# GPS_radiologger_v24_L70_CMWX_MAX.net
KiCad netlist of a schematic drawn in EAGLE
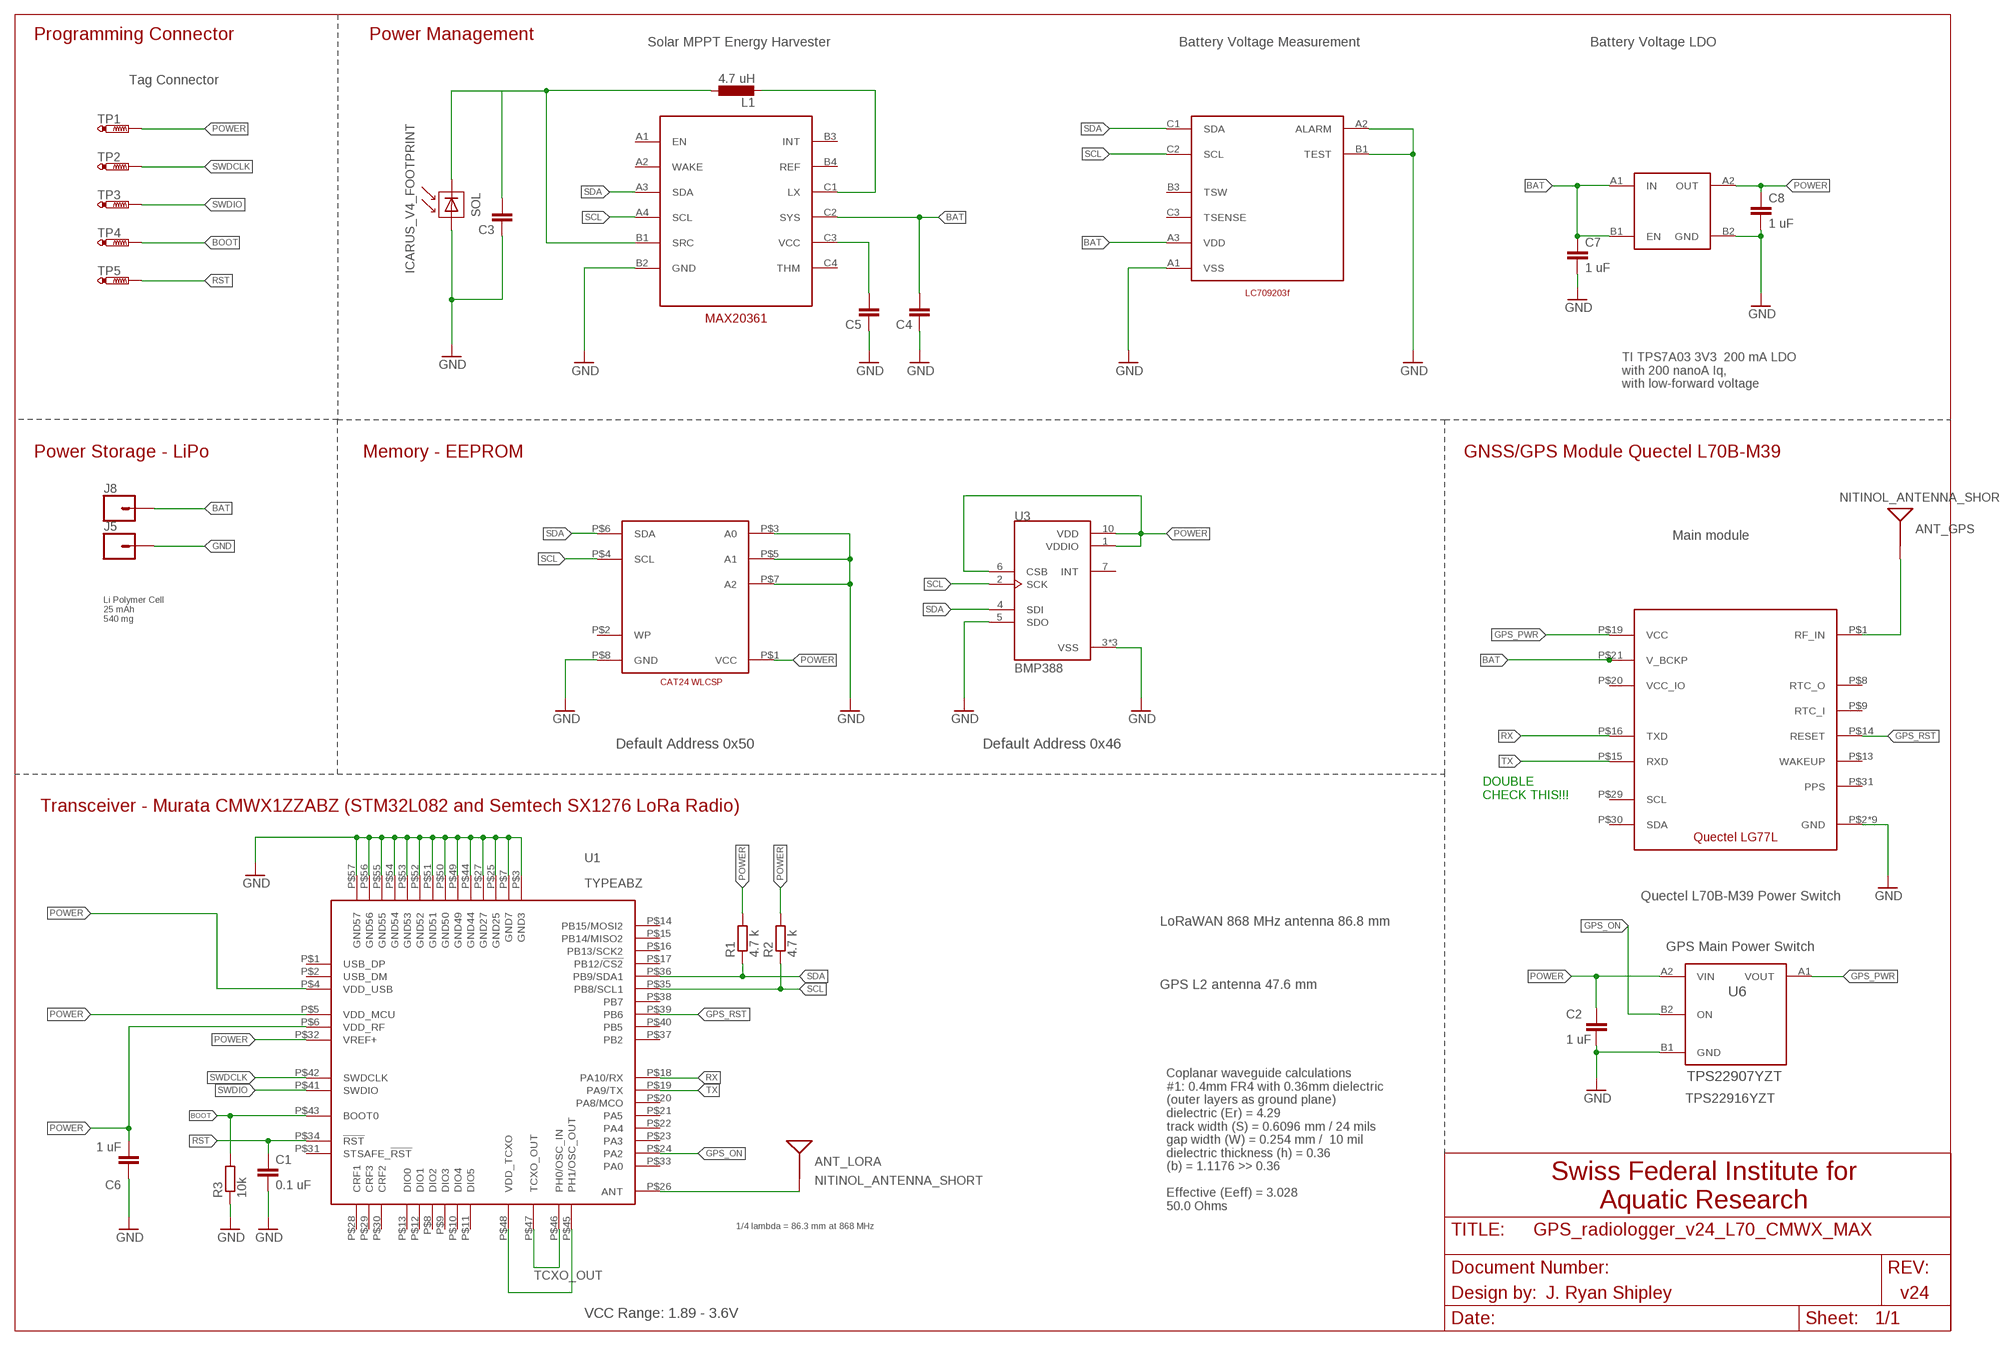
[diagram p0: schematic, sheet 1]

(export (version "E")
  (design (tool "Eeschema 10.0.6"))
  (components
    (comp (ref "ANT_GPS")
      (value "NITINOL_ANTENNA_SHORT")
      (footprint "eagle-import:ICARUS_NITINOL_ANTENNA_SHORT")
      (libsource (lib "eagle-import") (part "NITINOL_ANTENNA_SHORT"))
    )
    (comp (ref "ANT_LORA")
      (value "NITINOL_ANTENNA_SHORT")
      (footprint "eagle-import:ICARUS_NITINOL_ANTENNA_SHORT")
      (libsource (lib "eagle-import") (part "NITINOL_ANTENNA_SHORT"))
    )
    (comp (ref "C1")
      (value "0.1 uF")
      (footprint "eagle-import:C0201")
      (libsource (lib "eagle-import") (part "C-EUC0201"))
    )
    (comp (ref "C2")
      (value "1 uF")
      (footprint "eagle-import:C0201")
      (libsource (lib "eagle-import") (part "C-EUC0201"))
    )
    (comp (ref "C3")
      (value "10UF")
      (footprint "eagle-import:0603-TIGHT")
      (libsource (lib "eagle-import") (part "10UF"))
    )
    (comp (ref "C4")
      (value "1.0UF")
      (footprint "eagle-import:0402-TIGHTER")
      (libsource (lib "eagle-import") (part "1.0UF"))
    )
    (comp (ref "C5")
      (value "1.0UF")
      (footprint "eagle-import:0402-TIGHTER")
      (libsource (lib "eagle-import") (part "1.0UF"))
    )
    (comp (ref "C6")
      (value "1 uF")
      (footprint "eagle-import:C0201")
      (libsource (lib "eagle-import") (part "C-EUC0201"))
    )
    (comp (ref "C7")
      (value "1 uF")
      (footprint "eagle-import:0402-CAP")
      (libsource (lib "eagle-import") (part "0402CAP.KW"))
    )
    (comp (ref "C8")
      (value "1 uF")
      (footprint "eagle-import:0402-CAP")
      (libsource (lib "eagle-import") (part "0402CAP.KW"))
    )
    (comp (ref "J5")
      (value "CONN_01PTH_NO_SILK_SMALL")
      (footprint "eagle-import:1X01_SMALL")
      (libsource (lib "eagle-import") (part "CONN_01PTH_NO_SILK_SMALL"))
    )
    (comp (ref "J8")
      (value "CONN_01PTH_NO_SILK_SMALL")
      (footprint "eagle-import:1X01_SMALL")
      (libsource (lib "eagle-import") (part "CONN_01PTH_NO_SILK_SMALL"))
    )
    (comp (ref "L1")
      (value "4.7 uH")
      (footprint "eagle-import:INDC2016X120L")
      (libsource (lib "eagle-import") (part "IND_2016"))
    )
    (comp (ref "R1")
      (value "4.7 k")
      (footprint "eagle-import:R0201")
      (libsource (lib "eagle-import") (part "R-EU_R0201"))
    )
    (comp (ref "R2")
      (value "4.7 k")
      (footprint "eagle-import:R0201")
      (libsource (lib "eagle-import") (part "R-EU_R0201"))
    )
    (comp (ref "R3")
      (value "10k")
      (footprint "eagle-import:R0201")
      (libsource (lib "eagle-import") (part "R-EU_R0201"))
    )
    (comp (ref "SOL")
      (value "ICARUS_V4_FOOTPRINT")
      (footprint "eagle-import:ICARUS_FULL_FOOTPRINT")
      (libsource (lib "eagle-import") (part "ICARUS_V4_FOOTPRINT"))
    )
    (comp (ref "TP1")
      (value "PTR1TP08SQ")
      (footprint "eagle-import:TP08SQ")
      (libsource (lib "eagle-import") (part "PTR1TP08SQ"))
    )
    (comp (ref "TP2")
      (value "PTR1TP08SQ")
      (footprint "eagle-import:TP08SQ")
      (libsource (lib "eagle-import") (part "PTR1TP08SQ"))
    )
    (comp (ref "TP3")
      (value "PTR1TP08SQ")
      (footprint "eagle-import:TP08SQ")
      (libsource (lib "eagle-import") (part "PTR1TP08SQ"))
    )
    (comp (ref "TP4")
      (value "PTR1TP08SQ")
      (footprint "eagle-import:TP08SQ")
      (libsource (lib "eagle-import") (part "PTR1TP08SQ"))
    )
    (comp (ref "TP5")
      (value "PTR1TP08SQ")
      (footprint "eagle-import:TP08SQ")
      (libsource (lib "eagle-import") (part "PTR1TP08SQ"))
    )
    (comp (ref "U$1")
      (value "LG77L")
      (footprint "eagle-import:LG77L")
      (libsource (lib "eagle-import") (part "LG77L"))
    )
    (comp (ref "U1")
      (value "TYPEABZ")
      (footprint "eagle-import:TYPEABZ")
      (libsource (lib "eagle-import") (part "TYPEABZ"))
    )
    (comp (ref "U3")
      (value "BMP388")
      (footprint "eagle-import:PQFN50P200X200X80-10N")
      (fields (field (name "MF") "Bosch Sensortec"))
      (libsource (lib "eagle-import") (part "BMP388"))
    )
    (comp (ref "U4")
      (value "TPS7A03-DSBGA")
      (footprint "eagle-import:BGA4N35P2X2_70X70X40N")
      (libsource (lib "eagle-import") (part "TPS7A03-DSBGA"))
    )
    (comp (ref "U5")
      (value "LC709203F")
      (footprint "eagle-import:BGA9N50P3X3_160X175X50N")
      (libsource (lib "eagle-import") (part "LC709203F"))
    )
    (comp (ref "U6")
      (value "TPS22907YZT")
      (footprint "eagle-import:YFP0004-DSBGA")
      (libsource (lib "eagle-import") (part "TPS22907YZT"))
    )
    (comp (ref "U7")
      (value "CAT24_WLCSP8")
      (footprint "eagle-import:WLCSP8")
      (libsource (lib "eagle-import") (part "CAT24_WLCSP8"))
    )
    (comp (ref "U8")
      (value "MAX20361")
      (footprint "eagle-import:BGA12N40P4X3_123X163X64N")
      (libsource (lib "eagle-import") (part "MAX20361"))
    )
  )
  (nets
    (net (code "1") (name "/TCXO_OUT") (class "Default")
      (node (ref "U1") (pin "P$46") (pinfunction "PH0/OSC_IN_P$46") (pintype "bidirectional"))
      (node (ref "U1") (pin "P$47") (pinfunction "TCXO_OUT_P$47") (pintype "bidirectional"))
    )
    (net (code "2") (name "BAT") (class "Default")
      (node (ref "C4") (pin "P$2") (pinfunction "2_P$2") (pintype "passive"))
      (node (ref "C7") (pin "1") (pinfunction "1_1") (pintype "passive"))
      (node (ref "J8") (pin "P$1") (pinfunction "1_P$1") (pintype "passive"))
      (node (ref "U$1") (pin "P$21") (pinfunction "V_BCKP_P$21") (pintype "bidirectional"))
      (node (ref "U4") (pin "A1") (pinfunction "IN_A1") (pintype "bidirectional"))
      (node (ref "U4") (pin "B1") (pinfunction "EN_B1") (pintype "bidirectional"))
      (node (ref "U5") (pin "A3") (pinfunction "VDD_A3") (pintype "bidirectional"))
      (node (ref "U8") (pin "C2") (pinfunction "SYS_C2") (pintype "bidirectional"))
    )
    (net (code "3") (name "BOOT") (class "Default")
      (node (ref "R3") (pin "2") (pinfunction "2_2") (pintype "passive"))
      (node (ref "TP4") (pin "TP") (pinfunction "TP_TP") (pintype "input"))
      (node (ref "U1") (pin "P$43") (pinfunction "BOOT0_P$43") (pintype "bidirectional"))
    )
    (net (code "4") (name "GND") (class "Default")
      (node (ref "C1") (pin "2") (pinfunction "2_2") (pintype "passive"))
      (node (ref "C2") (pin "2") (pinfunction "2_2") (pintype "passive"))
      (node (ref "C3") (pin "P$1") (pinfunction "1_P$1") (pintype "passive"))
      (node (ref "C4") (pin "P$1") (pinfunction "1_P$1") (pintype "passive"))
      (node (ref "C5") (pin "P$1") (pinfunction "1_P$1") (pintype "passive"))
      (node (ref "C6") (pin "1") (pinfunction "1_1") (pintype "passive"))
      (node (ref "C7") (pin "2") (pinfunction "2_2") (pintype "passive"))
      (node (ref "C8") (pin "2") (pinfunction "2_2") (pintype "passive"))
      (node (ref "J5") (pin "P$1") (pinfunction "1_P$1") (pintype "passive"))
      (node (ref "R3") (pin "1") (pinfunction "1_1") (pintype "passive"))
      (node (ref "SOL") (pin "P$2") (pinfunction "MINUS_P$2") (pintype "passive"))
      (node (ref "U$1") (pin "P$18") (pinfunction "GND_P$18") (pintype "bidirectional"))
      (node (ref "U$1") (pin "P$2") (pinfunction "GND_P$2") (pintype "bidirectional"))
      (node (ref "U$1") (pin "P$37") (pinfunction "GND_P$37") (pintype "bidirectional"))
      (node (ref "U$1") (pin "P$38") (pinfunction "GND_P$38") (pintype "bidirectional"))
      (node (ref "U$1") (pin "P$39") (pinfunction "GND_P$39") (pintype "bidirectional"))
      (node (ref "U$1") (pin "P$40") (pinfunction "GND_P$40") (pintype "bidirectional"))
      (node (ref "U$1") (pin "P$41") (pinfunction "GND_P$41") (pintype "bidirectional"))
      (node (ref "U$1") (pin "P$42") (pinfunction "GND_P$42") (pintype "bidirectional"))
      (node (ref "U$1") (pin "P$43") (pinfunction "GND_P$43") (pintype "bidirectional"))
      (node (ref "U1") (pin "P$25") (pinfunction "GND25_P$25") (pintype "power_in"))
      (node (ref "U1") (pin "P$27") (pinfunction "GND27_P$27") (pintype "power_in"))
      (node (ref "U1") (pin "P$3") (pinfunction "GND3_P$3") (pintype "power_in"))
      (node (ref "U1") (pin "P$44") (pinfunction "GND44_P$44") (pintype "power_in"))
      (node (ref "U1") (pin "P$49") (pinfunction "GND49_P$49") (pintype "power_in"))
      (node (ref "U1") (pin "P$50") (pinfunction "GND50_P$50") (pintype "power_in"))
      (node (ref "U1") (pin "P$51") (pinfunction "GND51_P$51") (pintype "power_in"))
      (node (ref "U1") (pin "P$52") (pinfunction "GND52_P$52") (pintype "power_in"))
      (node (ref "U1") (pin "P$53") (pinfunction "GND53_P$53") (pintype "power_in"))
      (node (ref "U1") (pin "P$54") (pinfunction "GND54_P$54") (pintype "power_in"))
      (node (ref "U1") (pin "P$55") (pinfunction "GND55_P$55") (pintype "power_in"))
      (node (ref "U1") (pin "P$56") (pinfunction "GND56_P$56") (pintype "power_in"))
      (node (ref "U1") (pin "P$57") (pinfunction "GND57_P$57") (pintype "power_in"))
      (node (ref "U1") (pin "P$7") (pinfunction "GND7_P$7") (pintype "power_in"))
      (node (ref "U3") (pin "3") (pinfunction "VSS_3") (pintype "power_in"))
      (node (ref "U3") (pin "5") (pinfunction "SDO_5") (pintype "bidirectional"))
      (node (ref "U3") (pin "8") (pinfunction "VSS_8") (pintype "power_in"))
      (node (ref "U3") (pin "9") (pinfunction "VSS_9") (pintype "power_in"))
      (node (ref "U4") (pin "B2") (pinfunction "GND_B2") (pintype "bidirectional"))
      (node (ref "U5") (pin "A1") (pinfunction "VSS_A1") (pintype "bidirectional"))
      (node (ref "U5") (pin "A2") (pinfunction "ALARM_A2") (pintype "bidirectional"))
      (node (ref "U5") (pin "B1") (pinfunction "TEST_B1") (pintype "bidirectional"))
      (node (ref "U6") (pin "B1") (pinfunction "GND_B1") (pintype "bidirectional"))
      (node (ref "U7") (pin "P$3") (pinfunction "A0_P$3") (pintype "bidirectional"))
      (node (ref "U7") (pin "P$5") (pinfunction "A1_P$5") (pintype "bidirectional"))
      (node (ref "U7") (pin "P$7") (pinfunction "A2_P$7") (pintype "bidirectional"))
      (node (ref "U7") (pin "P$8") (pinfunction "GND_P$8") (pintype "bidirectional"))
      (node (ref "U8") (pin "B2") (pinfunction "GND_B2") (pintype "bidirectional"))
    )
    (net (code "5") (name "GPS_ON") (class "Default")
      (node (ref "U1") (pin "P$24") (pinfunction "PA2_P$24") (pintype "bidirectional"))
      (node (ref "U6") (pin "B2") (pinfunction "ON_B2") (pintype "bidirectional"))
    )
    (net (code "6") (name "GPS_PWR") (class "Default")
      (node (ref "U$1") (pin "P$19") (pinfunction "VCC_P$19") (pintype "bidirectional"))
      (node (ref "U6") (pin "A1") (pinfunction "VOUT_A1") (pintype "bidirectional"))
    )
    (net (code "7") (name "GPS_RST") (class "Default")
      (node (ref "U$1") (pin "P$14") (pinfunction "RESET_P$14") (pintype "bidirectional"))
      (node (ref "U1") (pin "P$39") (pinfunction "PB6_P$39") (pintype "bidirectional"))
    )
    (net (code "8") (name "Net-(C3-2)") (class "Default")
      (node (ref "C3") (pin "P$2") (pinfunction "2_P$2") (pintype "passive"))
      (node (ref "L1") (pin "1") (pinfunction "1_1") (pintype "passive"))
      (node (ref "SOL") (pin "P$1") (pinfunction "PLUS_P$1") (pintype "passive"))
      (node (ref "U8") (pin "B1") (pinfunction "SRC_B1") (pintype "bidirectional"))
    )
    (net (code "9") (name "Net-(C5-2)") (class "Default")
      (node (ref "C5") (pin "P$2") (pinfunction "2_P$2") (pintype "passive"))
      (node (ref "U8") (pin "C3") (pinfunction "VCC_C3") (pintype "bidirectional"))
    )
    (net (code "10") (name "Net-(U$1-RF_IN)") (class "Default")
      (node (ref "ANT_GPS") (pin "1") (pinfunction "SIGNAL_1") (pintype "bidirectional"))
      (node (ref "ANT_GPS") (pin "2") (pinfunction "SIGNAL_2") (pintype "bidirectional"))
      (node (ref "ANT_GPS") (pin "3") (pinfunction "SIGNAL_3") (pintype "bidirectional"))
      (node (ref "U$1") (pin "P$1") (pinfunction "RF_IN_P$1") (pintype "bidirectional"))
    )
    (net (code "11") (name "Net-(U1-ANT)") (class "Default")
      (node (ref "ANT_LORA") (pin "1") (pinfunction "SIGNAL_1") (pintype "bidirectional"))
      (node (ref "ANT_LORA") (pin "2") (pinfunction "SIGNAL_2") (pintype "bidirectional"))
      (node (ref "ANT_LORA") (pin "3") (pinfunction "SIGNAL_3") (pintype "bidirectional"))
      (node (ref "U1") (pin "P$26") (pinfunction "ANT_P$26") (pintype "bidirectional"))
    )
    (net (code "12") (name "Net-(U1-PH1{slash}OSC_OUT)") (class "Default")
      (node (ref "U1") (pin "P$45") (pinfunction "PH1/OSC_OUT_P$45") (pintype "bidirectional"))
      (node (ref "U1") (pin "P$48") (pinfunction "VDD_TCXO_P$48") (pintype "power_in"))
    )
    (net (code "13") (name "Net-(U8-LX)") (class "Default")
      (node (ref "L1") (pin "2") (pinfunction "2_2") (pintype "passive"))
      (node (ref "U8") (pin "C1") (pinfunction "LX_C1") (pintype "bidirectional"))
    )
    (net (code "14") (name "POWER") (class "Default")
      (node (ref "C2") (pin "1") (pinfunction "1_1") (pintype "passive"))
      (node (ref "C6") (pin "2") (pinfunction "2_2") (pintype "passive"))
      (node (ref "C8") (pin "1") (pinfunction "1_1") (pintype "passive"))
      (node (ref "R1") (pin "2") (pinfunction "2_2") (pintype "passive"))
      (node (ref "R2") (pin "2") (pinfunction "2_2") (pintype "passive"))
      (node (ref "TP1") (pin "TP") (pinfunction "TP_TP") (pintype "input"))
      (node (ref "U1") (pin "P$32") (pinfunction "VREF+_P$32") (pintype "power_in"))
      (node (ref "U1") (pin "P$4") (pinfunction "VDD_USB_P$4") (pintype "power_in"))
      (node (ref "U1") (pin "P$5") (pinfunction "VDD_MCU_P$5") (pintype "power_in"))
      (node (ref "U1") (pin "P$6") (pinfunction "VDD_RF_P$6") (pintype "power_in"))
      (node (ref "U3") (pin "1") (pinfunction "VDDIO_1") (pintype "power_in"))
      (node (ref "U3") (pin "10") (pinfunction "VDD_10") (pintype "power_in"))
      (node (ref "U3") (pin "6") (pinfunction "CSB_6") (pintype "input"))
      (node (ref "U4") (pin "A2") (pinfunction "OUT_A2") (pintype "bidirectional"))
      (node (ref "U6") (pin "A2") (pinfunction "VIN_A2") (pintype "bidirectional"))
      (node (ref "U7") (pin "P$1") (pinfunction "VCC_P$1") (pintype "bidirectional"))
    )
    (net (code "15") (name "RST") (class "Default")
      (node (ref "C1") (pin "1") (pinfunction "1_1") (pintype "passive"))
      (node (ref "TP5") (pin "TP") (pinfunction "TP_TP") (pintype "input"))
      (node (ref "U1") (pin "P$34") (pinfunction "~{RST}_P$34") (pintype "bidirectional"))
    )
    (net (code "16") (name "RX") (class "Default")
      (node (ref "U$1") (pin "P$16") (pinfunction "TXD_P$16") (pintype "bidirectional"))
      (node (ref "U1") (pin "P$18") (pinfunction "PA10/RX_P$18") (pintype "bidirectional"))
    )
    (net (code "17") (name "SCL") (class "Default")
      (node (ref "R2") (pin "1") (pinfunction "1_1") (pintype "passive"))
      (node (ref "U1") (pin "P$35") (pinfunction "PB8/SCL1_P$35") (pintype "bidirectional"))
      (node (ref "U3") (pin "2") (pinfunction "SCK_2") (pintype "input"))
      (node (ref "U5") (pin "C2") (pinfunction "SCL_C2") (pintype "bidirectional"))
      (node (ref "U7") (pin "P$4") (pinfunction "SCL_P$4") (pintype "bidirectional"))
      (node (ref "U8") (pin "A4") (pinfunction "SCL_A4") (pintype "bidirectional"))
    )
    (net (code "18") (name "SDA") (class "Default")
      (node (ref "R1") (pin "1") (pinfunction "1_1") (pintype "passive"))
      (node (ref "U1") (pin "P$36") (pinfunction "PB9/SDA1_P$36") (pintype "bidirectional"))
      (node (ref "U3") (pin "4") (pinfunction "SDI_4") (pintype "bidirectional"))
      (node (ref "U5") (pin "C1") (pinfunction "SDA_C1") (pintype "bidirectional"))
      (node (ref "U7") (pin "P$6") (pinfunction "SDA_P$6") (pintype "bidirectional"))
      (node (ref "U8") (pin "A3") (pinfunction "SDA_A3") (pintype "bidirectional"))
    )
    (net (code "19") (name "SWDCLK") (class "Default")
      (node (ref "TP2") (pin "TP") (pinfunction "TP_TP") (pintype "input"))
      (node (ref "U1") (pin "P$42") (pinfunction "SWDCLK_P$42") (pintype "bidirectional"))
    )
    (net (code "20") (name "SWDIO") (class "Default")
      (node (ref "TP3") (pin "TP") (pinfunction "TP_TP") (pintype "input"))
      (node (ref "U1") (pin "P$41") (pinfunction "SWDIO_P$41") (pintype "bidirectional"))
    )
    (net (code "21") (name "TX") (class "Default")
      (node (ref "U$1") (pin "P$15") (pinfunction "RXD_P$15") (pintype "bidirectional"))
      (node (ref "U1") (pin "P$19") (pinfunction "PA9/TX_P$19") (pintype "bidirectional"))
    )
    (net (code "22") (name "unconnected-(U$1-PPS-PadP$31)") (class "Default")
      (node (ref "U$1") (pin "P$31") (pinfunction "PPS_P$31") (pintype "bidirectional"))
    )
    (net (code "23") (name "unconnected-(U$1-RTC_I-PadP$9)") (class "Default")
      (node (ref "U$1") (pin "P$9") (pinfunction "RTC_I_P$9") (pintype "bidirectional"))
    )
    (net (code "24") (name "unconnected-(U$1-RTC_O-PadP$8)") (class "Default")
      (node (ref "U$1") (pin "P$8") (pinfunction "RTC_O_P$8") (pintype "bidirectional"))
    )
    (net (code "25") (name "unconnected-(U$1-SCL-PadP$29)") (class "Default")
      (node (ref "U$1") (pin "P$29") (pinfunction "SCL_P$29") (pintype "bidirectional"))
    )
    (net (code "26") (name "unconnected-(U$1-SDA-PadP$30)") (class "Default")
      (node (ref "U$1") (pin "P$30") (pinfunction "SDA_P$30") (pintype "bidirectional"))
    )
    (net (code "27") (name "unconnected-(U$1-VCC_IO-PadP$20)") (class "Default")
      (node (ref "U$1") (pin "P$20") (pinfunction "VCC_IO_P$20") (pintype "bidirectional"))
    )
    (net (code "28") (name "unconnected-(U$1-WAKEUP-PadP$13)") (class "Default")
      (node (ref "U$1") (pin "P$13") (pinfunction "WAKEUP_P$13") (pintype "bidirectional"))
    )
    (net (code "29") (name "unconnected-(U1-CRF1-PadP$28)") (class "Default")
      (node (ref "U1") (pin "P$28") (pinfunction "CRF1_P$28") (pintype "no_connect"))
    )
    (net (code "30") (name "unconnected-(U1-CRF2-PadP$30)") (class "Default")
      (node (ref "U1") (pin "P$30") (pinfunction "CRF2_P$30") (pintype "no_connect"))
    )
    (net (code "31") (name "unconnected-(U1-CRF3-PadP$29)") (class "Default")
      (node (ref "U1") (pin "P$29") (pinfunction "CRF3_P$29") (pintype "no_connect"))
    )
    (net (code "32") (name "unconnected-(U1-DIO0-PadP$13)") (class "Default")
      (node (ref "U1") (pin "P$13") (pinfunction "DIO0_P$13") (pintype "no_connect"))
    )
    (net (code "33") (name "unconnected-(U1-DIO1-PadP$12)") (class "Default")
      (node (ref "U1") (pin "P$12") (pinfunction "DIO1_P$12") (pintype "no_connect"))
    )
    (net (code "34") (name "unconnected-(U1-DIO2-PadP$8)") (class "Default")
      (node (ref "U1") (pin "P$8") (pinfunction "DIO2_P$8") (pintype "no_connect"))
    )
    (net (code "35") (name "unconnected-(U1-DIO3-PadP$9)") (class "Default")
      (node (ref "U1") (pin "P$9") (pinfunction "DIO3_P$9") (pintype "no_connect"))
    )
    (net (code "36") (name "unconnected-(U1-DIO4-PadP$10)") (class "Default")
      (node (ref "U1") (pin "P$10") (pinfunction "DIO4_P$10") (pintype "bidirectional"))
    )
    (net (code "37") (name "unconnected-(U1-DIO5-PadP$11)") (class "Default")
      (node (ref "U1") (pin "P$11") (pinfunction "DIO5_P$11") (pintype "bidirectional"))
    )
    (net (code "38") (name "unconnected-(U1-PA0-PadP$33)") (class "Default")
      (node (ref "U1") (pin "P$33") (pinfunction "PA0_P$33") (pintype "bidirectional"))
    )
    (net (code "39") (name "unconnected-(U1-PA3-PadP$23)") (class "Default")
      (node (ref "U1") (pin "P$23") (pinfunction "PA3_P$23") (pintype "bidirectional"))
    )
    (net (code "40") (name "unconnected-(U1-PA4-PadP$22)") (class "Default")
      (node (ref "U1") (pin "P$22") (pinfunction "PA4_P$22") (pintype "bidirectional"))
    )
    (net (code "41") (name "unconnected-(U1-PA5-PadP$21)") (class "Default")
      (node (ref "U1") (pin "P$21") (pinfunction "PA5_P$21") (pintype "bidirectional"))
    )
    (net (code "42") (name "unconnected-(U1-PA8{slash}MCO-PadP$20)") (class "Default")
      (node (ref "U1") (pin "P$20") (pinfunction "PA8/MCO_P$20") (pintype "bidirectional"))
    )
    (net (code "43") (name "unconnected-(U1-PB2-PadP$37)") (class "Default")
      (node (ref "U1") (pin "P$37") (pinfunction "PB2_P$37") (pintype "bidirectional"))
    )
    (net (code "44") (name "unconnected-(U1-PB5-PadP$40)") (class "Default")
      (node (ref "U1") (pin "P$40") (pinfunction "PB5_P$40") (pintype "bidirectional"))
    )
    (net (code "45") (name "unconnected-(U1-PB7-PadP$38)") (class "Default")
      (node (ref "U1") (pin "P$38") (pinfunction "PB7_P$38") (pintype "bidirectional"))
    )
    (net (code "46") (name "unconnected-(U1-PB12{slash}~{CS2}-PadP$17)") (class "Default")
      (node (ref "U1") (pin "P$17") (pinfunction "PB12/~{CS2}_P$17") (pintype "bidirectional"))
    )
    (net (code "47") (name "unconnected-(U1-PB13{slash}SCK2-PadP$16)") (class "Default")
      (node (ref "U1") (pin "P$16") (pinfunction "PB13/SCK2_P$16") (pintype "bidirectional"))
    )
    (net (code "48") (name "unconnected-(U1-PB14{slash}MISO2-PadP$15)") (class "Default")
      (node (ref "U1") (pin "P$15") (pinfunction "PB14/MISO2_P$15") (pintype "bidirectional"))
    )
    (net (code "49") (name "unconnected-(U1-PB15{slash}MOSI2-PadP$14)") (class "Default")
      (node (ref "U1") (pin "P$14") (pinfunction "PB15/MOSI2_P$14") (pintype "bidirectional"))
    )
    (net (code "50") (name "unconnected-(U1-STSAFE_~{RST}-PadP$31)") (class "Default")
      (node (ref "U1") (pin "P$31") (pinfunction "STSAFE_~{RST}_P$31") (pintype "bidirectional"))
    )
    (net (code "51") (name "unconnected-(U1-USB_DM-PadP$2)") (class "Default")
      (node (ref "U1") (pin "P$2") (pinfunction "USB_DM_P$2") (pintype "bidirectional"))
    )
    (net (code "52") (name "unconnected-(U1-USB_DP-PadP$1)") (class "Default")
      (node (ref "U1") (pin "P$1") (pinfunction "USB_DP_P$1") (pintype "bidirectional"))
    )
    (net (code "53") (name "unconnected-(U3-INT-Pad7)") (class "Default")
      (node (ref "U3") (pin "7") (pinfunction "INT_7") (pintype "output"))
    )
    (net (code "54") (name "unconnected-(U5-TSENSE-PadC3)") (class "Default")
      (node (ref "U5") (pin "C3") (pinfunction "TSENSE_C3") (pintype "bidirectional"))
    )
    (net (code "55") (name "unconnected-(U5-TSW-PadB3)") (class "Default")
      (node (ref "U5") (pin "B3") (pinfunction "TSW_B3") (pintype "bidirectional"))
    )
    (net (code "56") (name "unconnected-(U7-WP-PadP$2)") (class "Default")
      (node (ref "U7") (pin "P$2") (pinfunction "WP_P$2") (pintype "bidirectional"))
    )
    (net (code "57") (name "unconnected-(U8-EN-PadA1)") (class "Default")
      (node (ref "U8") (pin "A1") (pinfunction "EN_A1") (pintype "bidirectional"))
    )
    (net (code "58") (name "unconnected-(U8-INT-PadB3)") (class "Default")
      (node (ref "U8") (pin "B3") (pinfunction "INT_B3") (pintype "bidirectional"))
    )
    (net (code "59") (name "unconnected-(U8-REF-PadB4)") (class "Default")
      (node (ref "U8") (pin "B4") (pinfunction "REF_B4") (pintype "bidirectional"))
    )
    (net (code "60") (name "unconnected-(U8-THM-PadC4)") (class "Default")
      (node (ref "U8") (pin "C4") (pinfunction "THM_C4") (pintype "bidirectional"))
    )
    (net (code "61") (name "unconnected-(U8-WAKE-PadA2)") (class "Default")
      (node (ref "U8") (pin "A2") (pinfunction "WAKE_A2") (pintype "bidirectional"))
    )
  )
)
